# CLK_buffer.net
KiCad netlist of a schematic drawn in Altium Designer
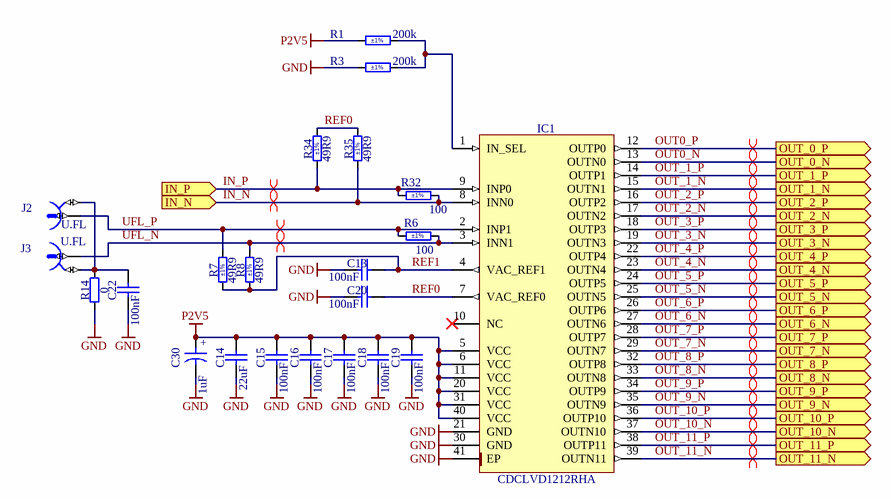
[diagram p0: CLK_buffer.SchDoc]

(export (version "E")
  (design (tool "Eeschema 10.0.6"))
  (components
    (comp (ref "C13")
      (value "100nF")
      (footprint "CAPC1005X55N")
      (description "Non-polarised capacitor")
      (fields
        (field (name "PART NUMBER") "CC0402_100NF_50V_10%_X7R")
        (field (name "VOLTAGE") "50V")
        (field (name "AUTHOR") "CERN DEM MR")
      )
      (libsource (lib "Capacitors") (part "Capacitor - non polarized"))
    )
    (comp (ref "C14")
      (value "22uF")
      (footprint "CAPC2012X135N")
      (description "Non-polarised capacitor")
      (fields
        (field (name "PART NUMBER") "CC0805_22UF_16V_10%_X5R")
        (field (name "VOLTAGE") "16V")
        (field (name "AUTHOR") "CERN DEM JLC")
      )
      (libsource (lib "Capacitors") (part "Capacitor - non polarized"))
    )
    (comp (ref "C15")
      (value "100nF")
      (footprint "CAPC1005X55N")
      (description "Non-polarised capacitor")
      (fields
        (field (name "PART NUMBER") "CC0402_100NF_50V_10%_X7R")
        (field (name "VOLTAGE") "50V")
        (field (name "AUTHOR") "CERN DEM MR")
      )
      (libsource (lib "Capacitors") (part "Capacitor - non polarized"))
    )
    (comp (ref "C16")
      (value "100nF")
      (footprint "CAPC1005X55N")
      (description "Non-polarised capacitor")
      (fields
        (field (name "PART NUMBER") "CC0402_100NF_50V_10%_X7R")
        (field (name "VOLTAGE") "50V")
        (field (name "AUTHOR") "CERN DEM MR")
      )
      (libsource (lib "Capacitors") (part "Capacitor - non polarized"))
    )
    (comp (ref "C17")
      (value "100nF")
      (footprint "CAPC1005X55N")
      (description "Non-polarised capacitor")
      (fields
        (field (name "PART NUMBER") "CC0402_100NF_50V_10%_X7R")
        (field (name "VOLTAGE") "50V")
        (field (name "AUTHOR") "CERN DEM MR")
      )
      (libsource (lib "Capacitors") (part "Capacitor - non polarized"))
    )
    (comp (ref "C18")
      (value "100nF")
      (footprint "CAPC1005X55N")
      (description "Non-polarised capacitor")
      (fields
        (field (name "PART NUMBER") "CC0402_100NF_50V_10%_X7R")
        (field (name "VOLTAGE") "50V")
        (field (name "AUTHOR") "CERN DEM MR")
      )
      (libsource (lib "Capacitors") (part "Capacitor - non polarized"))
    )
    (comp (ref "C19")
      (value "100nF")
      (footprint "CAPC1005X55N")
      (description "Non-polarised capacitor")
      (fields
        (field (name "PART NUMBER") "CC0402_100NF_50V_10%_X7R")
        (field (name "VOLTAGE") "50V")
        (field (name "AUTHOR") "CERN DEM MR")
      )
      (libsource (lib "Capacitors") (part "Capacitor - non polarized"))
    )
    (comp (ref "C20")
      (value "100nF")
      (footprint "CAPC1005X55N")
      (description "Non-polarised capacitor")
      (fields
        (field (name "PART NUMBER") "CC0402_100NF_50V_10%_X7R")
        (field (name "VOLTAGE") "50V")
        (field (name "AUTHOR") "CERN DEM MR")
      )
      (libsource (lib "Capacitors") (part "Capacitor - non polarized"))
    )
    (comp (ref "C22")
      (value "100nF")
      (footprint "CAPC1005X55N")
      (description "Non-polarised capacitor")
      (fields
        (field (name "PART NUMBER") "CC0402_100NF_50V_10%_X7R")
        (field (name "VOLTAGE") "50V")
        (field (name "AUTHOR") "CERN DEM MR")
      )
      (libsource (lib "Capacitors") (part "Capacitor - non polarized"))
    )
    (comp (ref "C30")
      (value "1uF")
      (footprint "CAPMP3216X180N")
      (description "Polarised capacitor")
      (fields
        (field (name "PART NUMBER") "CTE3216-18_1UF_16V_10%")
        (field (name "VOLTAGE") "16V")
        (field (name "AUTHOR") "CERN DEM JLC")
      )
      (libsource (lib "Capacitors") (part "Capacitor - polarized"))
    )
    (comp (ref "IC1")
      (value "CDCLVD1212RHA")
      (footprint "QFN50P600X600X100-41N-S425")
      (description "2:12 Low Additive Jitter LVDS Buffer")
      (fields (field (name "MANUFACTURER") "TEXAS INSTRUMENTS") (field (name "AUTHOR") "CERN DEM MR"))
      (libsource (lib "ICs And Semiconductors") (part "CDCLVD1212"))
    )
    (comp (ref "J2")
      (value "U.FL")
      (footprint "HIROSE_U.FL-R-SMT-1(10)")
      (fields
        (field (name "MANUFACTURER PART NUMBER") "U.FL-R-SMT-1(10)")
        (field (name "MANUFACTURER") "HIROSE (HRS)")
        (field (name "PART NUMBER") "HIROSE_U.FL-R-SMT-1(10)")
        (field (name "AUTHOR") "CERN DEM JLC")
      )
      (libsource (lib "") (part "Coax_1Male_1Shield_1"))
    )
    (comp (ref "J3")
      (value "U.FL")
      (footprint "HIROSE_U.FL-R-SMT-1(10)")
      (fields
        (field (name "MANUFACTURER PART NUMBER") "U.FL-R-SMT-1(10)")
        (field (name "MANUFACTURER") "HIROSE (HRS)")
        (field (name "PART NUMBER") "HIROSE_U.FL-R-SMT-1(10)")
        (field (name "AUTHOR") "CERN DEM JLC")
      )
      (libsource (lib "Connectors") (part "Coax_1Male_1Shield"))
    )
    (comp (ref "R1")
      (value "200k")
      (footprint "RESC1005X40N")
      (description "Resistor - 1%")
      (fields
        (field (name "TOLERANCE") "±1%")
        (field (name "PART NUMBER") "R0402_200K_1%_0.0625W_100PPM")
        (field (name "POWER") "0.0625W")
        (field (name "AUTHOR") "CERN DEM JLC")
      )
      (libsource (lib "Resistors") (part "Resistor - 1%"))
    )
    (comp (ref "R3")
      (value "200k")
      (footprint "RESC1005X40N")
      (description "Resistor - 1%")
      (fields
        (field (name "TOLERANCE") "±1%")
        (field (name "PART NUMBER") "R0402_200K_1%_0.0625W_100PPM")
        (field (name "POWER") "0.0625W")
        (field (name "AUTHOR") "CERN DEM JLC")
      )
      (libsource (lib "Resistors") (part "Resistor - 1%"))
    )
    (comp (ref "R6")
      (value "100")
      (footprint "RESC1005X40N")
      (description "Resistor - 1%")
      (fields
        (field (name "TOLERANCE") "±1%")
        (field (name "PART NUMBER") "R0402_100R_1%_0.0625W_100PPM")
        (field (name "POWER") "0.0625W")
        (field (name "AUTHOR") "CERN DEM JLC")
      )
      (libsource (lib "Resistors") (part "Resistor - 1%"))
    )
    (comp (ref "R7")
      (value "49R9")
      (footprint "RESC1005X40N")
      (description "Resistor - 1%")
      (fields
        (field (name "TOLERANCE") "±1%")
        (field (name "PART NUMBER") "R0402_49R9_1%_0.0625W_100PPM")
        (field (name "POWER") "0.0625W")
        (field (name "AUTHOR") "CERN DEM JLC")
      )
      (libsource (lib "Resistors") (part "Resistor - 1%"))
    )
    (comp (ref "R8")
      (value "49R9")
      (footprint "RESC1005X40N")
      (description "Resistor - 1%")
      (fields
        (field (name "TOLERANCE") "±1%")
        (field (name "PART NUMBER") "R0402_49R9_1%_0.0625W_100PPM")
        (field (name "POWER") "0.0625W")
        (field (name "AUTHOR") "CERN DEM JLC")
      )
      (libsource (lib "Resistors") (part "Resistor - 1%"))
    )
    (comp (ref "R14")
      (value "0")
      (footprint "RESC1005X40N")
      (description "Resistor")
      (fields
        (field (name "MANUFACTURER PART NUMBER") "R0402_0R_JUMPER")
        (field (name "MANUFACTURER") "GENERIC")
        (field (name "AUTHOR") "CERN DEM JLC")
      )
      (libsource (lib "Resistors") (part "Resistor"))
    )
    (comp (ref "R32")
      (value "100")
      (footprint "RESC1005X40N")
      (description "Resistor - 1%")
      (fields
        (field (name "TOLERANCE") "±1%")
        (field (name "PART NUMBER") "R0402_100R_1%_0.0625W_100PPM")
        (field (name "POWER") "0.0625W")
        (field (name "AUTHOR") "CERN DEM JLC")
      )
      (libsource (lib "Resistors") (part "Resistor - 1%"))
    )
    (comp (ref "R34")
      (value "49R9")
      (footprint "RESC1005X40N")
      (description "Resistor - 1%")
      (fields
        (field (name "TOLERANCE") "±1%")
        (field (name "PART NUMBER") "R0402_49R9_1%_0.0625W_100PPM")
        (field (name "POWER") "0.0625W")
        (field (name "AUTHOR") "CERN DEM JLC")
      )
      (libsource (lib "Resistors") (part "Resistor - 1%"))
    )
    (comp (ref "R35")
      (value "49R9")
      (footprint "RESC1005X40N")
      (description "Resistor - 1%")
      (fields
        (field (name "TOLERANCE") "±1%")
        (field (name "PART NUMBER") "R0402_49R9_1%_0.0625W_100PPM")
        (field (name "POWER") "0.0625W")
        (field (name "AUTHOR") "CERN DEM JLC")
      )
      (libsource (lib "Resistors") (part "Resistor - 1%"))
    )
  )
  (nets
    (net (code "1") (name "/IN_N") (class "Default")
      (node (ref "IC1") (pin "8") (pinfunction "INN0_8") (pintype "input"))
      (node (ref "R32") (pin "2") (pinfunction "2_2") (pintype "passive"))
      (node (ref "R35") (pin "1") (pinfunction "1_1") (pintype "passive"))
    )
    (net (code "2") (name "/IN_P") (class "Default")
      (node (ref "IC1") (pin "9") (pinfunction "INP0_9") (pintype "input"))
      (node (ref "R32") (pin "1") (pinfunction "1_1") (pintype "passive"))
      (node (ref "R34") (pin "1") (pinfunction "1_1") (pintype "passive"))
    )
    (net (code "3") (name "/OUT0_N") (class "Default")
      (node (ref "IC1") (pin "13") (pinfunction "OUTN0_13") (pintype "output"))
    )
    (net (code "4") (name "/OUT0_P") (class "Default")
      (node (ref "IC1") (pin "12") (pinfunction "OUTP0_12") (pintype "output"))
    )
    (net (code "5") (name "/OUT_1_N") (class "Default")
      (node (ref "IC1") (pin "15") (pinfunction "OUTN1_15") (pintype "output"))
    )
    (net (code "6") (name "/OUT_1_P") (class "Default")
      (node (ref "IC1") (pin "14") (pinfunction "OUTP1_14") (pintype "output"))
    )
    (net (code "7") (name "/OUT_2_N") (class "Default")
      (node (ref "IC1") (pin "17") (pinfunction "OUTN2_17") (pintype "output"))
    )
    (net (code "8") (name "/OUT_2_P") (class "Default")
      (node (ref "IC1") (pin "16") (pinfunction "OUTP2_16") (pintype "output"))
    )
    (net (code "9") (name "/OUT_3_N") (class "Default")
      (node (ref "IC1") (pin "19") (pinfunction "OUTN3_19") (pintype "output"))
    )
    (net (code "10") (name "/OUT_3_P") (class "Default")
      (node (ref "IC1") (pin "18") (pinfunction "OUTP3_18") (pintype "output"))
    )
    (net (code "11") (name "/OUT_4_P") (class "Default")
      (node (ref "IC1") (pin "22") (pinfunction "OUTP4_22") (pintype "output"))
    )
    (net (code "12") (name "/OUT_5_N") (class "Default")
      (node (ref "IC1") (pin "25") (pinfunction "OUTN5_25") (pintype "output"))
    )
    (net (code "13") (name "/OUT_5_P") (class "Default")
      (node (ref "IC1") (pin "24") (pinfunction "OUTP5_24") (pintype "output"))
    )
    (net (code "14") (name "/OUT_6_N") (class "Default")
      (node (ref "IC1") (pin "27") (pinfunction "OUTN6_27") (pintype "output"))
    )
    (net (code "15") (name "/OUT_6_P") (class "Default")
      (node (ref "IC1") (pin "26") (pinfunction "OUTP6_26") (pintype "output"))
    )
    (net (code "16") (name "/OUT_7_N") (class "Default")
      (node (ref "IC1") (pin "29") (pinfunction "OUTN7_29") (pintype "output"))
    )
    (net (code "17") (name "/OUT_7_P") (class "Default")
      (node (ref "IC1") (pin "28") (pinfunction "OUTP7_28") (pintype "output"))
    )
    (net (code "18") (name "/OUT_8_N") (class "Default")
      (node (ref "IC1") (pin "33") (pinfunction "OUTN8_33") (pintype "output"))
    )
    (net (code "19") (name "/OUT_8_P") (class "Default")
      (node (ref "IC1") (pin "32") (pinfunction "OUTP8_32") (pintype "output"))
    )
    (net (code "20") (name "/OUT_9_N") (class "Default")
      (node (ref "IC1") (pin "35") (pinfunction "OUTN9_35") (pintype "output"))
    )
    (net (code "21") (name "/OUT_9_P") (class "Default")
      (node (ref "IC1") (pin "34") (pinfunction "OUTP9_34") (pintype "output"))
    )
    (net (code "22") (name "/OUT_10_N") (class "Default")
      (node (ref "IC1") (pin "37") (pinfunction "OUTN10_37") (pintype "output"))
    )
    (net (code "23") (name "/OUT_10_P") (class "Default")
      (node (ref "IC1") (pin "36") (pinfunction "OUTP10_36") (pintype "output"))
    )
    (net (code "24") (name "/OUT_11_N") (class "Default")
      (node (ref "IC1") (pin "39") (pinfunction "OUTN11_39") (pintype "output"))
    )
    (net (code "25") (name "/OUT_11_P") (class "Default")
      (node (ref "IC1") (pin "38") (pinfunction "OUTP11_38") (pintype "output"))
    )
    (net (code "26") (name "/OUT_~{4}_N") (class "Default")
      (node (ref "IC1") (pin "23") (pinfunction "OUTN4_23") (pintype "output"))
    )
    (net (code "27") (name "/REF0") (class "Default")
      (node (ref "C20") (pin "2") (pinfunction "2_2") (pintype "passive"))
      (node (ref "IC1") (pin "7") (pinfunction "VAC_REF0_7") (pintype "output"))
      (node (ref "R34") (pin "2") (pinfunction "2_2") (pintype "passive"))
      (node (ref "R35") (pin "2") (pinfunction "2_2") (pintype "passive"))
    )
    (net (code "28") (name "/REF1") (class "Default")
      (node (ref "C13") (pin "2") (pinfunction "2_2") (pintype "passive"))
      (node (ref "IC1") (pin "4") (pinfunction "VAC_REF1_4") (pintype "output"))
      (node (ref "R7") (pin "1") (pinfunction "1_1") (pintype "passive"))
      (node (ref "R8") (pin "1") (pinfunction "1_1") (pintype "passive"))
    )
    (net (code "29") (name "/UFL_N") (class "Default")
      (node (ref "IC1") (pin "3") (pinfunction "INN1_3") (pintype "input"))
      (node (ref "J3") (pin "1") (pinfunction "1_1") (pintype "bidirectional"))
      (node (ref "R6") (pin "2") (pinfunction "2_2") (pintype "passive"))
      (node (ref "R8") (pin "2") (pinfunction "2_2") (pintype "passive"))
    )
    (net (code "30") (name "/UFL_P") (class "Default")
      (node (ref "IC1") (pin "2") (pinfunction "INP1_2") (pintype "input"))
      (node (ref "J2") (pin "1") (pinfunction "1_1") (pintype "bidirectional"))
      (node (ref "R6") (pin "1") (pinfunction "1_1") (pintype "passive"))
      (node (ref "R7") (pin "2") (pinfunction "2_2") (pintype "passive"))
    )
    (net (code "31") (name "GND") (class "Default")
      (node (ref "C13") (pin "1") (pinfunction "1_1") (pintype "passive"))
      (node (ref "C14") (pin "1") (pinfunction "1_1") (pintype "passive"))
      (node (ref "C15") (pin "1") (pinfunction "1_1") (pintype "passive"))
      (node (ref "C16") (pin "1") (pinfunction "1_1") (pintype "passive"))
      (node (ref "C17") (pin "1") (pinfunction "1_1") (pintype "passive"))
      (node (ref "C18") (pin "1") (pinfunction "1_1") (pintype "passive"))
      (node (ref "C19") (pin "1") (pinfunction "1_1") (pintype "passive"))
      (node (ref "C20") (pin "1") (pinfunction "1_1") (pintype "passive"))
      (node (ref "C22") (pin "1") (pinfunction "1_1") (pintype "passive"))
      (node (ref "C30") (pin "2") (pinfunction "2_2") (pintype "passive"))
      (node (ref "IC1") (pin "21") (pinfunction "GND_21") (pintype "passive"))
      (node (ref "IC1") (pin "30") (pinfunction "GND_30") (pintype "power_in"))
      (node (ref "IC1") (pin "41") (pinfunction "EP_41") (pintype "power_in"))
      (node (ref "R14") (pin "1") (pinfunction "1_1") (pintype "passive"))
      (node (ref "R3") (pin "1") (pinfunction "1_1") (pintype "passive"))
    )
    (net (code "32") (name "Net-(C22-Pad2)") (class "Default")
      (node (ref "C22") (pin "2") (pinfunction "2_2") (pintype "passive"))
      (node (ref "J2") (pin "2") (pinfunction "2_2") (pintype "bidirectional"))
      (node (ref "J3") (pin "2") (pinfunction "2_2") (pintype "bidirectional"))
      (node (ref "R14") (pin "2") (pinfunction "2_2") (pintype "passive"))
    )
    (net (code "33") (name "Net-(IC1-IN_SEL)") (class "Default")
      (node (ref "IC1") (pin "1") (pinfunction "IN_SEL_1") (pintype "input"))
      (node (ref "R1") (pin "2") (pinfunction "2_2") (pintype "passive"))
      (node (ref "R3") (pin "2") (pinfunction "2_2") (pintype "passive"))
    )
    (net (code "34") (name "P2V5") (class "Default")
      (node (ref "C14") (pin "2") (pinfunction "2_2") (pintype "passive"))
      (node (ref "C15") (pin "2") (pinfunction "2_2") (pintype "passive"))
      (node (ref "C16") (pin "2") (pinfunction "2_2") (pintype "passive"))
      (node (ref "C17") (pin "2") (pinfunction "2_2") (pintype "passive"))
      (node (ref "C18") (pin "2") (pinfunction "2_2") (pintype "passive"))
      (node (ref "C19") (pin "2") (pinfunction "2_2") (pintype "passive"))
      (node (ref "C30") (pin "1") (pinfunction "1_1") (pintype "passive"))
      (node (ref "IC1") (pin "11") (pinfunction "VCC_11") (pintype "power_in"))
      (node (ref "IC1") (pin "20") (pinfunction "VCC_20") (pintype "power_in"))
      (node (ref "IC1") (pin "31") (pinfunction "VCC_31") (pintype "power_in"))
      (node (ref "IC1") (pin "40") (pinfunction "VCC_40") (pintype "power_in"))
      (node (ref "IC1") (pin "5") (pinfunction "VCC_5") (pintype "power_in"))
      (node (ref "IC1") (pin "6") (pinfunction "VCC_6") (pintype "power_in"))
      (node (ref "R1") (pin "1") (pinfunction "1_1") (pintype "passive"))
    )
    (net (code "35") (name "unconnected-(IC1-NC-Pad10)") (class "Default")
      (node (ref "IC1") (pin "10") (pinfunction "NC_10") (pintype "passive+no_connect"))
    )
  )
)
